# Power_Supplies.net
KiCad netlist of a schematic drawn in Altium Designer
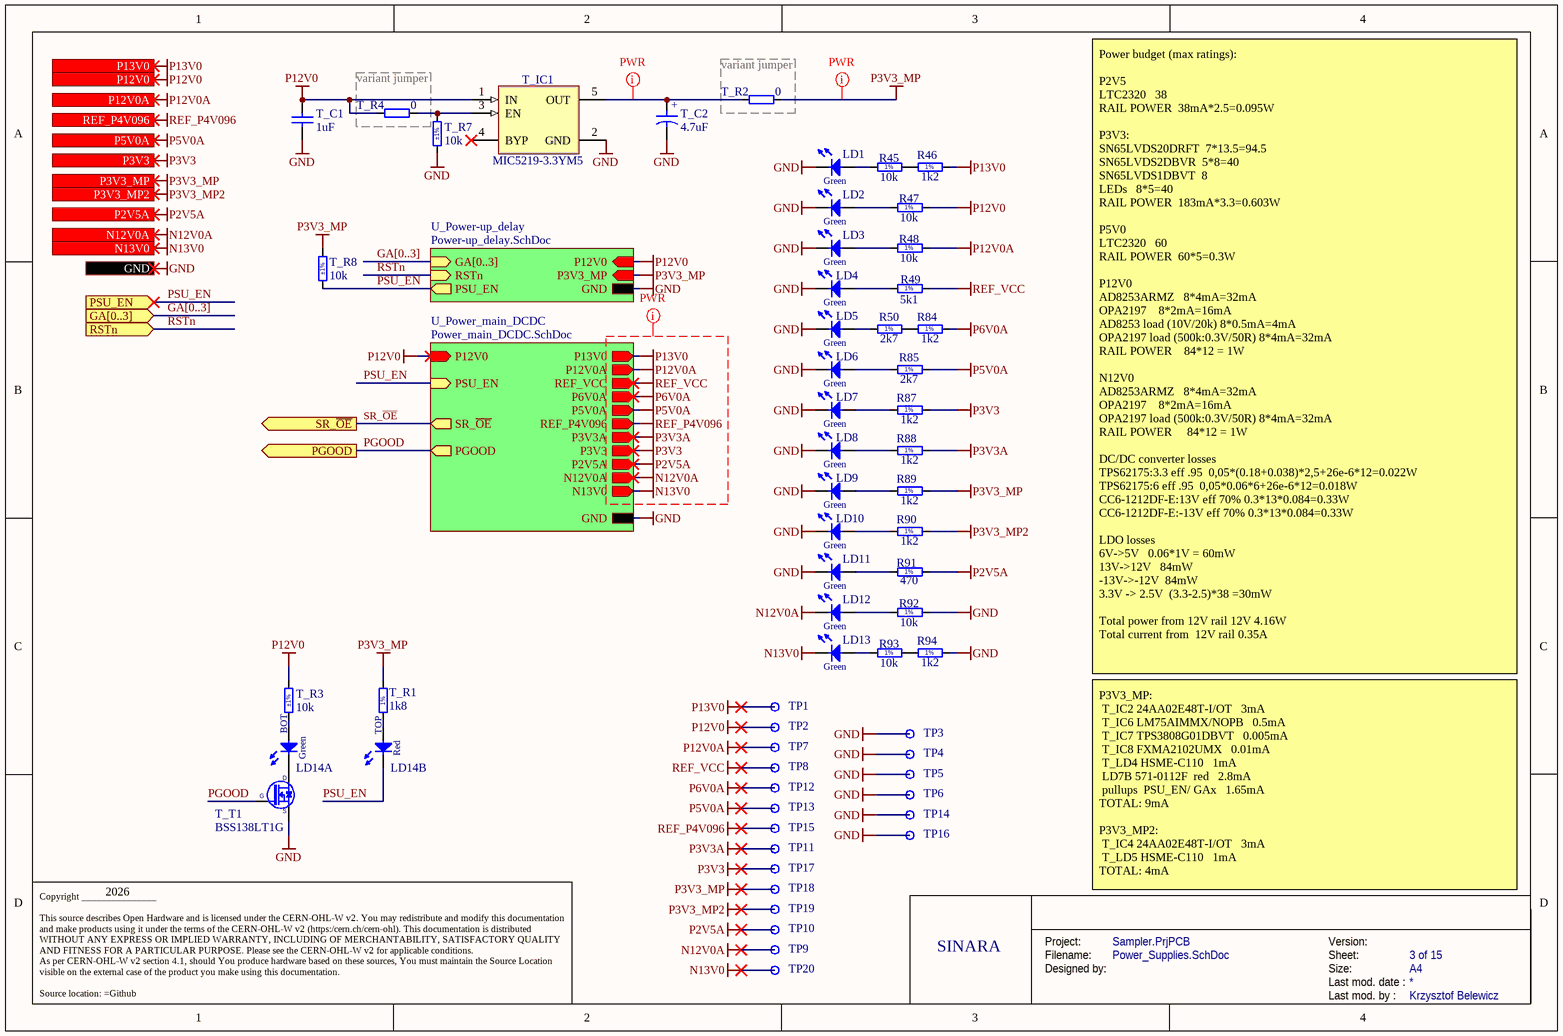
[diagram p0: Power_Supplies.SchDoc]

(export (version "E")
  (design (tool "Eeschema 10.0.6"))
  (components
    (comp (ref "LD1")
      (value "Green")
      (footprint "LED_KINGBRIGHT_KPH-1608CGCK")
      (description "LED Green 1C 2A")
      (fields
        (field (name "PART NUMBER") "LED_KINGBRIGHT_KPH-1608CGCK")
        (field (name "MANUFACTURER") "KINGBRIGHT")
        (field (name "AUTHOR") "CERN DEM JLC")
      )
      (libsource (lib "ICs And Semiconductors") (part "LED Green 1C 2A"))
    )
    (comp (ref "LD2")
      (value "Green")
      (footprint "LED_KINGBRIGHT_KPH-1608CGCK")
      (description "LED Green 1C 2A")
      (fields
        (field (name "PART NUMBER") "LED_KINGBRIGHT_KPH-1608CGCK")
        (field (name "MANUFACTURER") "KINGBRIGHT")
        (field (name "AUTHOR") "CERN DEM JLC")
      )
      (libsource (lib "ICs And Semiconductors") (part "LED Green 1C 2A"))
    )
    (comp (ref "LD3")
      (value "Green")
      (footprint "LED_KINGBRIGHT_KPH-1608CGCK")
      (description "LED Green 1C 2A")
      (fields
        (field (name "PART NUMBER") "LED_KINGBRIGHT_KPH-1608CGCK")
        (field (name "MANUFACTURER") "KINGBRIGHT")
        (field (name "AUTHOR") "CERN DEM JLC")
      )
      (libsource (lib "ICs And Semiconductors") (part "LED Green 1C 2A"))
    )
    (comp (ref "LD4")
      (value "Green")
      (footprint "LED_KINGBRIGHT_KPH-1608CGCK")
      (description "LED Green 1C 2A")
      (fields
        (field (name "PART NUMBER") "LED_KINGBRIGHT_KPH-1608CGCK")
        (field (name "MANUFACTURER") "KINGBRIGHT")
        (field (name "AUTHOR") "CERN DEM JLC")
      )
      (libsource (lib "ICs And Semiconductors") (part "LED Green 1C 2A"))
    )
    (comp (ref "LD5")
      (value "Green")
      (footprint "LED_KINGBRIGHT_KPH-1608CGCK")
      (description "LED Green 1C 2A")
      (fields
        (field (name "PART NUMBER") "LED_KINGBRIGHT_KPH-1608CGCK")
        (field (name "MANUFACTURER") "KINGBRIGHT")
        (field (name "AUTHOR") "CERN DEM JLC")
      )
      (libsource (lib "ICs And Semiconductors") (part "LED Green 1C 2A"))
    )
    (comp (ref "LD6")
      (value "Green")
      (footprint "LED_KINGBRIGHT_KPH-1608CGCK")
      (description "LED Green 1C 2A")
      (fields
        (field (name "PART NUMBER") "LED_KINGBRIGHT_KPH-1608CGCK")
        (field (name "MANUFACTURER") "KINGBRIGHT")
        (field (name "AUTHOR") "CERN DEM JLC")
      )
      (libsource (lib "ICs And Semiconductors") (part "LED Green 1C 2A"))
    )
    (comp (ref "LD7")
      (value "Green")
      (footprint "LED_KINGBRIGHT_KPH-1608CGCK")
      (description "LED Green 1C 2A")
      (fields
        (field (name "PART NUMBER") "LED_KINGBRIGHT_KPH-1608CGCK")
        (field (name "MANUFACTURER") "KINGBRIGHT")
        (field (name "AUTHOR") "CERN DEM JLC")
      )
      (libsource (lib "ICs And Semiconductors") (part "LED Green 1C 2A"))
    )
    (comp (ref "LD8")
      (value "Green")
      (footprint "LED_KINGBRIGHT_KPH-1608CGCK")
      (description "LED Green 1C 2A")
      (fields
        (field (name "PART NUMBER") "LED_KINGBRIGHT_KPH-1608CGCK")
        (field (name "MANUFACTURER") "KINGBRIGHT")
        (field (name "AUTHOR") "CERN DEM JLC")
      )
      (libsource (lib "ICs And Semiconductors") (part "LED Green 1C 2A"))
    )
    (comp (ref "LD9")
      (value "Green")
      (footprint "LED_KINGBRIGHT_KPH-1608CGCK")
      (description "LED Green 1C 2A")
      (fields
        (field (name "PART NUMBER") "LED_KINGBRIGHT_KPH-1608CGCK")
        (field (name "MANUFACTURER") "KINGBRIGHT")
        (field (name "AUTHOR") "CERN DEM JLC")
      )
      (libsource (lib "ICs And Semiconductors") (part "LED Green 1C 2A"))
    )
    (comp (ref "LD10")
      (value "Green")
      (footprint "LED_KINGBRIGHT_KPH-1608CGCK")
      (description "LED Green 1C 2A")
      (fields
        (field (name "PART NUMBER") "LED_KINGBRIGHT_KPH-1608CGCK")
        (field (name "MANUFACTURER") "KINGBRIGHT")
        (field (name "AUTHOR") "CERN DEM JLC")
      )
      (libsource (lib "ICs And Semiconductors") (part "LED Green 1C 2A"))
    )
    (comp (ref "LD11")
      (value "Green")
      (footprint "LED_KINGBRIGHT_KPH-1608CGCK")
      (description "LED Green 1C 2A")
      (fields
        (field (name "PART NUMBER") "LED_KINGBRIGHT_KPH-1608CGCK")
        (field (name "MANUFACTURER") "KINGBRIGHT")
        (field (name "AUTHOR") "CERN DEM JLC")
      )
      (libsource (lib "ICs And Semiconductors") (part "LED Green 1C 2A"))
    )
    (comp (ref "LD12")
      (value "Green")
      (footprint "LED_KINGBRIGHT_KPH-1608CGCK")
      (description "LED Green 1C 2A")
      (fields
        (field (name "PART NUMBER") "LED_KINGBRIGHT_KPH-1608CGCK")
        (field (name "MANUFACTURER") "KINGBRIGHT")
        (field (name "AUTHOR") "CERN DEM JLC")
      )
      (libsource (lib "ICs And Semiconductors") (part "LED Green 1C 2A"))
    )
    (comp (ref "LD13")
      (value "Green")
      (footprint "LED_KINGBRIGHT_KPH-1608CGCK")
      (description "LED Green 1C 2A")
      (fields
        (field (name "PART NUMBER") "LED_KINGBRIGHT_KPH-1608CGCK")
        (field (name "MANUFACTURER") "KINGBRIGHT")
        (field (name "AUTHOR") "CERN DEM JLC")
      )
      (libsource (lib "ICs And Semiconductors") (part "LED Green 1C 2A"))
    )
    (comp (ref "LD14")
      (value "Red/Green")
      (footprint "LED_DIALIGHT_571-0112F")
      (description "2x LED  Botom Green, Top Red")
      (fields
        (field (name "PART NUMBER") "LED_DIALIGHT_571-0112F")
        (field (name "MANUFACTURER") "DIALIGHT")
        (field (name "AUTHOR") "CERN DEM JLC")
      )
      (libsource (lib "ICs And Semiconductors") (part "LED x2 G-1C2A-BOT_R-3C4A-TOP"))
    )
    (comp (ref "R45")
      (value "10k")
      (footprint "RESC1005X40N")
      (description "Resistor - 1%")
      (fields
        (field (name "PART NUMBER") "R0402_10K_1%_0.0625W_100PPM")
        (field (name "POWER") "0.0625W")
        (field (name "AUTHOR") "CERN DEM JLC")
      )
      (libsource (lib "") (part "Resistor - 1%_1"))
    )
    (comp (ref "R46")
      (value "1k2")
      (footprint "RESC1608X55N")
      (description "Resistor - 1%")
      (fields
        (field (name "PART NUMBER") "R0603_1K2_1%_0.1W_100PPM")
        (field (name "POWER") "0.1W")
        (field (name "AUTHOR") "CERN DEM JLC")
      )
      (libsource (lib "Resistors") (part "Resistor - 1%"))
    )
    (comp (ref "R47")
      (value "10k")
      (footprint "RESC1005X40N")
      (description "Resistor - 1%")
      (fields
        (field (name "PART NUMBER") "R0402_10K_1%_0.0625W_100PPM")
        (field (name "POWER") "0.0625W")
        (field (name "AUTHOR") "CERN DEM JLC")
      )
      (libsource (lib "") (part "Resistor - 1%_1"))
    )
    (comp (ref "R48")
      (value "10k")
      (footprint "RESC1005X40N")
      (description "Resistor - 1%")
      (fields
        (field (name "PART NUMBER") "R0402_10K_1%_0.0625W_100PPM")
        (field (name "POWER") "0.0625W")
        (field (name "AUTHOR") "CERN DEM JLC")
      )
      (libsource (lib "") (part "Resistor - 1%_1"))
    )
    (comp (ref "R49")
      (value "5k1")
      (footprint "RESC1005X40N")
      (description "Resistor - 1%")
      (fields
        (field (name "PART NUMBER") "R0402_5K1_1%_0.0625W_100PPM")
        (field (name "POWER") "0.0625W")
        (field (name "AUTHOR") "CERN DEM JLC")
      )
      (libsource (lib "") (part "Resistor - 1%_1"))
    )
    (comp (ref "R50")
      (value "2k7")
      (footprint "RESC1608X55N")
      (description "Resistor - 1%")
      (fields
        (field (name "PART NUMBER") "R0603_2K7_1%_0.1W_100PPM")
        (field (name "POWER") "0.1W")
        (field (name "AUTHOR") "CERN DEM JLC")
      )
      (libsource (lib "Resistors") (part "Resistor - 1%"))
    )
    (comp (ref "R84")
      (value "1k2")
      (footprint "RESC1608X55N")
      (description "Resistor - 1%")
      (fields
        (field (name "PART NUMBER") "R0603_1K2_1%_0.1W_100PPM")
        (field (name "POWER") "0.1W")
        (field (name "AUTHOR") "CERN DEM JLC")
      )
      (libsource (lib "Resistors") (part "Resistor - 1%"))
    )
    (comp (ref "R85")
      (value "2k7")
      (footprint "RESC1608X55N")
      (description "Resistor - 1%")
      (fields
        (field (name "PART NUMBER") "R0603_2K7_1%_0.1W_100PPM")
        (field (name "POWER") "0.1W")
        (field (name "AUTHOR") "CERN DEM JLC")
      )
      (libsource (lib "Resistors") (part "Resistor - 1%"))
    )
    (comp (ref "R87")
      (value "1k2")
      (footprint "RESC1608X55N")
      (description "Resistor - 1%")
      (fields
        (field (name "PART NUMBER") "R0603_1K2_1%_0.1W_100PPM")
        (field (name "POWER") "0.1W")
        (field (name "AUTHOR") "CERN DEM JLC")
      )
      (libsource (lib "Resistors") (part "Resistor - 1%"))
    )
    (comp (ref "R88")
      (value "1k2")
      (footprint "RESC1608X55N")
      (description "Resistor - 1%")
      (fields
        (field (name "PART NUMBER") "R0603_1K2_1%_0.1W_100PPM")
        (field (name "POWER") "0.1W")
        (field (name "AUTHOR") "CERN DEM JLC")
      )
      (libsource (lib "Resistors") (part "Resistor - 1%"))
    )
    (comp (ref "R89")
      (value "1k2")
      (footprint "RESC1608X55N")
      (description "Resistor - 1%")
      (fields
        (field (name "PART NUMBER") "R0603_1K2_1%_0.1W_100PPM")
        (field (name "POWER") "0.1W")
        (field (name "AUTHOR") "CERN DEM JLC")
      )
      (libsource (lib "Resistors") (part "Resistor - 1%"))
    )
    (comp (ref "R90")
      (value "1k2")
      (footprint "RESC1608X55N")
      (description "Resistor - 1%")
      (fields
        (field (name "PART NUMBER") "R0603_1K2_1%_0.1W_100PPM")
        (field (name "POWER") "0.1W")
        (field (name "AUTHOR") "CERN DEM JLC")
      )
      (libsource (lib "Resistors") (part "Resistor - 1%"))
    )
    (comp (ref "R91")
      (value "470")
      (footprint "RESC1005X40N")
      (description "Resistor - 1%")
      (fields
        (field (name "PART NUMBER") "R0402_470R_1%_0.0625W_100PPM")
        (field (name "POWER") "0.0625W")
        (field (name "AUTHOR") "CERN DEM JLC")
      )
      (libsource (lib "") (part "Resistor - 1%_1"))
    )
    (comp (ref "R92")
      (value "10k")
      (footprint "RESC1005X40N")
      (description "Resistor - 1%")
      (fields
        (field (name "PART NUMBER") "R0402_10K_1%_0.0625W_100PPM")
        (field (name "POWER") "0.0625W")
        (field (name "AUTHOR") "CERN DEM JLC")
      )
      (libsource (lib "") (part "Resistor - 1%_1"))
    )
    (comp (ref "R93")
      (value "10k")
      (footprint "RESC1005X40N")
      (description "Resistor - 1%")
      (fields
        (field (name "PART NUMBER") "R0402_10K_1%_0.0625W_100PPM")
        (field (name "POWER") "0.0625W")
        (field (name "AUTHOR") "CERN DEM JLC")
      )
      (libsource (lib "") (part "Resistor - 1%_1"))
    )
    (comp (ref "R94")
      (value "1k2")
      (footprint "RESC1608X55N")
      (description "Resistor - 1%")
      (fields
        (field (name "PART NUMBER") "R0603_1K2_1%_0.1W_100PPM")
        (field (name "POWER") "0.1W")
        (field (name "AUTHOR") "CERN DEM JLC")
      )
      (libsource (lib "Resistors") (part "Resistor - 1%"))
    )
    (comp (ref "TP1")
      (value "Test Point")
      (footprint "TPS127")
      (fields (field (name "PART NUMBER") "SMD_PAD_1.27X1.27MM") (field (name "AUTHOR") "CERN DEM JLC"))
      (libsource (lib "Eletro-mechanical") (part "Test Point"))
    )
    (comp (ref "TP2")
      (value "Test Point")
      (footprint "TPS127")
      (fields (field (name "PART NUMBER") "SMD_PAD_1.27X1.27MM") (field (name "AUTHOR") "CERN DEM JLC"))
      (libsource (lib "Eletro-mechanical") (part "Test Point"))
    )
    (comp (ref "TP3")
      (value "Test Point")
      (footprint "TPS127")
      (fields (field (name "PART NUMBER") "SMD_PAD_1.27X1.27MM") (field (name "AUTHOR") "CERN DEM JLC"))
      (libsource (lib "Eletro-mechanical") (part "Test Point"))
    )
    (comp (ref "TP4")
      (value "Test Point")
      (footprint "TPS127")
      (fields (field (name "PART NUMBER") "SMD_PAD_1.27X1.27MM") (field (name "AUTHOR") "CERN DEM JLC"))
      (libsource (lib "Eletro-mechanical") (part "Test Point"))
    )
    (comp (ref "TP5")
      (value "Test Point")
      (footprint "TPS127")
      (fields (field (name "PART NUMBER") "SMD_PAD_1.27X1.27MM") (field (name "AUTHOR") "CERN DEM JLC"))
      (libsource (lib "Eletro-mechanical") (part "Test Point"))
    )
    (comp (ref "TP6")
      (value "Test Point")
      (footprint "TPS127")
      (fields (field (name "PART NUMBER") "SMD_PAD_1.27X1.27MM") (field (name "AUTHOR") "CERN DEM JLC"))
      (libsource (lib "Eletro-mechanical") (part "Test Point"))
    )
    (comp (ref "TP7")
      (value "Test Point")
      (footprint "TPS127")
      (fields (field (name "PART NUMBER") "SMD_PAD_1.27X1.27MM") (field (name "AUTHOR") "CERN DEM JLC"))
      (libsource (lib "Eletro-mechanical") (part "Test Point"))
    )
    (comp (ref "TP8")
      (value "Test Point")
      (footprint "TPS127")
      (fields (field (name "PART NUMBER") "SMD_PAD_1.27X1.27MM") (field (name "AUTHOR") "CERN DEM JLC"))
      (libsource (lib "Eletro-mechanical") (part "Test Point"))
    )
    (comp (ref "TP9")
      (value "Test Point")
      (footprint "TPS127")
      (fields (field (name "PART NUMBER") "SMD_PAD_1.27X1.27MM") (field (name "AUTHOR") "CERN DEM JLC"))
      (libsource (lib "Eletro-mechanical") (part "Test Point"))
    )
    (comp (ref "TP10")
      (value "Test Point")
      (footprint "TPS127")
      (fields (field (name "PART NUMBER") "SMD_PAD_1.27X1.27MM") (field (name "AUTHOR") "CERN DEM JLC"))
      (libsource (lib "Eletro-mechanical") (part "Test Point"))
    )
    (comp (ref "TP11")
      (value "Test Point")
      (footprint "TPS127")
      (fields (field (name "PART NUMBER") "SMD_PAD_1.27X1.27MM") (field (name "AUTHOR") "CERN DEM JLC"))
      (libsource (lib "Eletro-mechanical") (part "Test Point"))
    )
    (comp (ref "TP12")
      (value "Test Point")
      (footprint "TPS127")
      (fields (field (name "PART NUMBER") "SMD_PAD_1.27X1.27MM") (field (name "AUTHOR") "CERN DEM JLC"))
      (libsource (lib "Eletro-mechanical") (part "Test Point"))
    )
    (comp (ref "TP13")
      (value "Test Point")
      (footprint "TPS127")
      (fields (field (name "PART NUMBER") "SMD_PAD_1.27X1.27MM") (field (name "AUTHOR") "CERN DEM JLC"))
      (libsource (lib "Eletro-mechanical") (part "Test Point"))
    )
    (comp (ref "TP14")
      (value "Test Point")
      (footprint "TPS127")
      (fields (field (name "PART NUMBER") "SMD_PAD_1.27X1.27MM") (field (name "AUTHOR") "CERN DEM JLC"))
      (libsource (lib "Eletro-mechanical") (part "Test Point"))
    )
    (comp (ref "TP15")
      (value "Test Point")
      (footprint "TPS127")
      (fields (field (name "PART NUMBER") "SMD_PAD_1.27X1.27MM") (field (name "AUTHOR") "CERN DEM JLC"))
      (libsource (lib "Eletro-mechanical") (part "Test Point"))
    )
    (comp (ref "TP16")
      (value "Test Point")
      (footprint "TPS127")
      (fields (field (name "PART NUMBER") "SMD_PAD_1.27X1.27MM") (field (name "AUTHOR") "CERN DEM JLC"))
      (libsource (lib "Eletro-mechanical") (part "Test Point"))
    )
    (comp (ref "TP17")
      (value "Test Point")
      (footprint "TPS127")
      (fields (field (name "PART NUMBER") "SMD_PAD_1.27X1.27MM") (field (name "AUTHOR") "CERN DEM JLC"))
      (libsource (lib "Eletro-mechanical") (part "Test Point"))
    )
    (comp (ref "TP18")
      (value "Test Point")
      (footprint "TPS127")
      (fields (field (name "PART NUMBER") "SMD_PAD_1.27X1.27MM") (field (name "AUTHOR") "CERN DEM JLC"))
      (libsource (lib "Eletro-mechanical") (part "Test Point"))
    )
    (comp (ref "TP19")
      (value "Test Point")
      (footprint "TPS127")
      (fields (field (name "PART NUMBER") "SMD_PAD_1.27X1.27MM") (field (name "AUTHOR") "CERN DEM JLC"))
      (libsource (lib "Eletro-mechanical") (part "Test Point"))
    )
    (comp (ref "TP20")
      (value "Test Point")
      (footprint "TPS127")
      (fields (field (name "PART NUMBER") "SMD_PAD_1.27X1.27MM") (field (name "AUTHOR") "CERN DEM JLC"))
      (libsource (lib "Eletro-mechanical") (part "Test Point"))
    )
    (comp (ref "T_C1")
      (value "1uF")
      (footprint "CAPC1608X87N")
      (description "Non-polarised capacitor")
      (fields
        (field (name "PART NUMBER") "CC0603_1UF_25V_10%_X7R")
        (field (name "VOLTAGE") "25V")
        (field (name "AUTHOR") "CERN DEM JLC")
      )
      (libsource (lib "Capacitors") (part "Capacitor - non polarized"))
    )
    (comp (ref "T_C2")
      (value "4.7uF")
      (footprint "CAPMP3216X180N")
      (description "Polarised capacitor")
      (fields
        (field (name "PART NUMBER") "CTE3216-18_4.7UF_10V_10%_AVX_TPSA475K010T1400")
        (field (name "VOLTAGE") "10V")
        (field (name "AUTHOR") "CERN DEM JLC")
      )
      (libsource (lib "Capacitors") (part "Capacitor - polarized"))
    )
    (comp (ref "T_IC1")
      (value "MIC5219-3.3YM5")
      (footprint "SOT95P280X145-5N")
      (description "500mA Peak Output LDO Regulator")
      (fields (field (name "MANUFACTURER") "MICROCHIP TECHNOLOGY") (field (name "AUTHOR") "CERN DEM WB"))
      (libsource (lib "ICs And Semiconductors") (part "MIC5219-X.XYM5"))
    )
    (comp (ref "T_R1")
      (value "1k8")
      (footprint "RESC1608X55N")
      (description "Resistor - 1%")
      (fields
        (field (name "PART NUMBER") "R0603_1K8_1%_0.1W_100PPM")
        (field (name "POWER") "0.1W")
        (field (name "AUTHOR") "CERN DEM JLC")
      )
      (libsource (lib "Resistors") (part "Resistor - 1%"))
    )
    (comp (ref "T_R2")
      (value "0")
      (footprint "RESC1005X40N")
      (description "Resistor")
      (fields
        (field (name "PART NUMBER") "R0402_0R_JUMPER")
        (field (name "MANUFACTURER") "GENERIC")
        (field (name "AUTHOR") "CERN DEM JLC")
      )
      (libsource (lib "Resistors") (part "Resistor"))
    )
    (comp (ref "T_R3")
      (value "10k")
      (footprint "RESC1005X40N")
      (description "Resistor - 1%")
      (fields
        (field (name "TOLERANCE") "±1%")
        (field (name "PART NUMBER") "R0402_10K_1%_0.0625W_100PPM")
        (field (name "POWER") "0.0625W")
        (field (name "AUTHOR") "CERN DEM JLC")
      )
      (libsource (lib "") (part "Resistor - 1%_1"))
    )
    (comp (ref "T_R4")
      (value "0")
      (footprint "RESC1005X40N")
      (description "Resistor")
      (fields
        (field (name "PART NUMBER") "R0402_0R_JUMPER")
        (field (name "MANUFACTURER") "GENERIC")
        (field (name "AUTHOR") "CERN DEM JLC")
      )
      (libsource (lib "Resistors") (part "Resistor"))
    )
    (comp (ref "T_R7")
      (value "10k")
      (footprint "RESC1005X40N")
      (description "Resistor - 1%")
      (fields
        (field (name "TOLERANCE") "±1%")
        (field (name "PART NUMBER") "R0402_10K_1%_0.0625W_100PPM")
        (field (name "POWER") "0.0625W")
        (field (name "AUTHOR") "CERN DEM JLC")
      )
      (libsource (lib "") (part "Resistor - 1%_1"))
    )
    (comp (ref "T_R8")
      (value "10k")
      (footprint "RESC1005X40N")
      (description "Resistor - 1%")
      (fields
        (field (name "TOLERANCE") "±1%")
        (field (name "PART NUMBER") "R0402_10K_1%_0.0625W_100PPM")
        (field (name "POWER") "0.0625W")
        (field (name "AUTHOR") "CERN DEM JLC")
      )
      (libsource (lib "") (part "Resistor - 1%_1"))
    )
    (comp (ref "T_T1")
      (value "BSS138LT1G")
      (footprint "SOT95P240X110-3N")
      (description "N-CHANNEL MOSFET WITH DIODE")
      (fields
        (field (name "MANUFACTURER") "ON SEMICONDUCTOR")
        (field (name "MANUFACTURER PART NUMBER") "BSS138L")
        (field (name "AUTHOR") "CERN DEM JLC")
      )
      (libsource (lib "ICs And Semiconductors") (part "N-MOSFET-D 1G 2S 3D"))
    )
  )
  (nets
    (net (code "6") (name "/PGOOD") (class "Default")
      (node (ref "T_T1") (pin "1") (pinfunction "G_1") (pintype "passive"))
    )
    (net (code "7") (name "/PSU_EN") (class "Default")
      (node (ref "LD14") (pin "3") (pinfunction "C_3") (pintype "passive"))
      (node (ref "T_R8") (pin "1") (pinfunction "1_1") (pintype "passive"))
    )
    (net (code "10") (name "GND") (class "Default")
      (node (ref "LD1") (pin "1") (pinfunction "C_1") (pintype "passive"))
      (node (ref "LD10") (pin "1") (pinfunction "C_1") (pintype "passive"))
      (node (ref "LD11") (pin "1") (pinfunction "C_1") (pintype "passive"))
      (node (ref "LD2") (pin "1") (pinfunction "C_1") (pintype "passive"))
      (node (ref "LD3") (pin "1") (pinfunction "C_1") (pintype "passive"))
      (node (ref "LD4") (pin "1") (pinfunction "C_1") (pintype "passive"))
      (node (ref "LD5") (pin "1") (pinfunction "C_1") (pintype "passive"))
      (node (ref "LD6") (pin "1") (pinfunction "C_1") (pintype "passive"))
      (node (ref "LD7") (pin "1") (pinfunction "C_1") (pintype "passive"))
      (node (ref "LD8") (pin "1") (pinfunction "C_1") (pintype "passive"))
      (node (ref "LD9") (pin "1") (pinfunction "C_1") (pintype "passive"))
      (node (ref "R92") (pin "2") (pinfunction "2_2") (pintype "passive"))
      (node (ref "R94") (pin "2") (pinfunction "2_2") (pintype "passive"))
      (node (ref "TP14") (pin "1") (pinfunction "1_1") (pintype "bidirectional"))
      (node (ref "TP16") (pin "1") (pinfunction "1_1") (pintype "bidirectional"))
      (node (ref "TP3") (pin "1") (pinfunction "1_1") (pintype "bidirectional"))
      (node (ref "TP4") (pin "1") (pinfunction "1_1") (pintype "bidirectional"))
      (node (ref "TP5") (pin "1") (pinfunction "1_1") (pintype "bidirectional"))
      (node (ref "TP6") (pin "1") (pinfunction "1_1") (pintype "bidirectional"))
      (node (ref "T_C1") (pin "1") (pinfunction "1_1") (pintype "passive"))
      (node (ref "T_C2") (pin "2") (pinfunction "2_2") (pintype "passive"))
      (node (ref "T_IC1") (pin "2") (pinfunction "GND_2") (pintype "power_in"))
      (node (ref "T_R7") (pin "1") (pinfunction "1_1") (pintype "passive"))
      (node (ref "T_T1") (pin "2") (pinfunction "S_2") (pintype "passive"))
    )
    (net (code "11") (name "N12V0A") (class "Default")
      (node (ref "LD12") (pin "1") (pinfunction "C_1") (pintype "passive"))
      (node (ref "TP9") (pin "1") (pinfunction "1_1") (pintype "bidirectional"))
    )
    (net (code "12") (name "N13V0") (class "Default")
      (node (ref "LD13") (pin "1") (pinfunction "C_1") (pintype "passive"))
      (node (ref "TP20") (pin "1") (pinfunction "1_1") (pintype "bidirectional"))
    )
    (net (code "13") (name "Net-(LD1-A)") (class "Default")
      (node (ref "LD1") (pin "2") (pinfunction "A_2") (pintype "passive"))
      (node (ref "R45") (pin "1") (pinfunction "1_1") (pintype "passive"))
    )
    (net (code "14") (name "Net-(LD2-A)") (class "Default")
      (node (ref "LD2") (pin "2") (pinfunction "A_2") (pintype "passive"))
      (node (ref "R47") (pin "1") (pinfunction "1_1") (pintype "passive"))
    )
    (net (code "15") (name "Net-(LD3-A)") (class "Default")
      (node (ref "LD3") (pin "2") (pinfunction "A_2") (pintype "passive"))
      (node (ref "R48") (pin "1") (pinfunction "1_1") (pintype "passive"))
    )
    (net (code "16") (name "Net-(LD4-A)") (class "Default")
      (node (ref "LD4") (pin "2") (pinfunction "A_2") (pintype "passive"))
      (node (ref "R49") (pin "1") (pinfunction "1_1") (pintype "passive"))
    )
    (net (code "17") (name "Net-(LD5-A)") (class "Default")
      (node (ref "LD5") (pin "2") (pinfunction "A_2") (pintype "passive"))
      (node (ref "R50") (pin "1") (pinfunction "1_1") (pintype "passive"))
    )
    (net (code "18") (name "Net-(LD6-A)") (class "Default")
      (node (ref "LD6") (pin "2") (pinfunction "A_2") (pintype "passive"))
      (node (ref "R85") (pin "1") (pinfunction "1_1") (pintype "passive"))
    )
    (net (code "19") (name "Net-(LD7-A)") (class "Default")
      (node (ref "LD7") (pin "2") (pinfunction "A_2") (pintype "passive"))
      (node (ref "R87") (pin "1") (pinfunction "1_1") (pintype "passive"))
    )
    (net (code "20") (name "Net-(LD8-A)") (class "Default")
      (node (ref "LD8") (pin "2") (pinfunction "A_2") (pintype "passive"))
      (node (ref "R88") (pin "1") (pinfunction "1_1") (pintype "passive"))
    )
    (net (code "21") (name "Net-(LD9-A)") (class "Default")
      (node (ref "LD9") (pin "2") (pinfunction "A_2") (pintype "passive"))
      (node (ref "R89") (pin "1") (pinfunction "1_1") (pintype "passive"))
    )
    (net (code "22") (name "Net-(LD10-A)") (class "Default")
      (node (ref "LD10") (pin "2") (pinfunction "A_2") (pintype "passive"))
      (node (ref "R90") (pin "1") (pinfunction "1_1") (pintype "passive"))
    )
    (net (code "23") (name "Net-(LD11-A)") (class "Default")
      (node (ref "LD11") (pin "2") (pinfunction "A_2") (pintype "passive"))
      (node (ref "R91") (pin "2") (pinfunction "2_2") (pintype "passive"))
    )
    (net (code "24") (name "Net-(LD12-A)") (class "Default")
      (node (ref "LD12") (pin "2") (pinfunction "A_2") (pintype "passive"))
      (node (ref "R92") (pin "1") (pinfunction "1_1") (pintype "passive"))
    )
    (net (code "25") (name "Net-(LD13-A)") (class "Default")
      (node (ref "LD13") (pin "2") (pinfunction "A_2") (pintype "passive"))
      (node (ref "R93") (pin "1") (pinfunction "1_1") (pintype "passive"))
    )
    (net (code "26") (name "Net-(LD14A-A)") (class "Default")
      (node (ref "LD14") (pin "2") (pinfunction "A_2") (pintype "passive"))
      (node (ref "T_R3") (pin "1") (pinfunction "1_1") (pintype "passive"))
    )
    (net (code "27") (name "Net-(LD14A-C)") (class "Default")
      (node (ref "LD14") (pin "1") (pinfunction "C_1") (pintype "passive"))
      (node (ref "T_T1") (pin "3") (pinfunction "D_3") (pintype "passive"))
    )
    (net (code "28") (name "Net-(LD14B-A)") (class "Default")
      (node (ref "LD14") (pin "4") (pinfunction "A_4") (pintype "passive"))
      (node (ref "T_R1") (pin "1") (pinfunction "1_1") (pintype "passive"))
    )
    (net (code "29") (name "Net-(R45-Pad2)") (class "Default")
      (node (ref "R45") (pin "2") (pinfunction "2_2") (pintype "passive"))
      (node (ref "R46") (pin "1") (pinfunction "1_1") (pintype "passive"))
    )
    (net (code "30") (name "Net-(R50-Pad2)") (class "Default")
      (node (ref "R50") (pin "2") (pinfunction "2_2") (pintype "passive"))
      (node (ref "R84") (pin "1") (pinfunction "1_1") (pintype "passive"))
    )
    (net (code "31") (name "Net-(R93-Pad2)") (class "Default")
      (node (ref "R93") (pin "2") (pinfunction "2_2") (pintype "passive"))
      (node (ref "R94") (pin "1") (pinfunction "1_1") (pintype "passive"))
    )
    (net (code "32") (name "Net-(T_IC1-EN)") (class "Default")
      (node (ref "T_IC1") (pin "3") (pinfunction "EN_3") (pintype "input"))
      (node (ref "T_R4") (pin "2") (pinfunction "2_2") (pintype "passive"))
      (node (ref "T_R7") (pin "2") (pinfunction "2_2") (pintype "passive"))
    )
    (net (code "33") (name "Net-(T_IC1-OUT)") (class "Default")
      (node (ref "T_C2") (pin "1") (pinfunction "1_1") (pintype "passive"))
      (node (ref "T_IC1") (pin "5") (pinfunction "OUT_5") (pintype "power_in"))
      (node (ref "T_R2") (pin "1") (pinfunction "1_1") (pintype "passive"))
    )
    (net (code "34") (name "P2V5A") (class "Default")
      (node (ref "R91") (pin "1") (pinfunction "1_1") (pintype "passive"))
      (node (ref "TP10") (pin "1") (pinfunction "1_1") (pintype "bidirectional"))
    )
    (net (code "35") (name "P3V3") (class "Default")
      (node (ref "R87") (pin "2") (pinfunction "2_2") (pintype "passive"))
      (node (ref "TP17") (pin "1") (pinfunction "1_1") (pintype "bidirectional"))
    )
    (net (code "36") (name "P3V3A") (class "Default")
      (node (ref "R88") (pin "2") (pinfunction "2_2") (pintype "passive"))
      (node (ref "TP11") (pin "1") (pinfunction "1_1") (pintype "bidirectional"))
    )
    (net (code "37") (name "P3V3_MP") (class "Default")
      (node (ref "R89") (pin "2") (pinfunction "2_2") (pintype "passive"))
      (node (ref "TP18") (pin "1") (pinfunction "1_1") (pintype "bidirectional"))
      (node (ref "T_R1") (pin "2") (pinfunction "2_2") (pintype "passive"))
      (node (ref "T_R2") (pin "2") (pinfunction "2_2") (pintype "passive"))
      (node (ref "T_R8") (pin "2") (pinfunction "2_2") (pintype "passive"))
    )
    (net (code "38") (name "P3V3_MP2") (class "Default")
      (node (ref "R90") (pin "2") (pinfunction "2_2") (pintype "passive"))
      (node (ref "TP19") (pin "1") (pinfunction "1_1") (pintype "bidirectional"))
    )
    (net (code "39") (name "P5V0A") (class "Default")
      (node (ref "R85") (pin "2") (pinfunction "2_2") (pintype "passive"))
      (node (ref "TP13") (pin "1") (pinfunction "1_1") (pintype "bidirectional"))
    )
    (net (code "40") (name "P6V0A") (class "Default")
      (node (ref "R84") (pin "2") (pinfunction "2_2") (pintype "passive"))
      (node (ref "TP12") (pin "1") (pinfunction "1_1") (pintype "bidirectional"))
    )
    (net (code "41") (name "P12V0") (class "Default")
      (node (ref "R47") (pin "2") (pinfunction "2_2") (pintype "passive"))
      (node (ref "TP2") (pin "1") (pinfunction "1_1") (pintype "bidirectional"))
      (node (ref "T_C1") (pin "2") (pinfunction "2_2") (pintype "passive"))
      (node (ref "T_IC1") (pin "1") (pinfunction "IN_1") (pintype "input"))
      (node (ref "T_R3") (pin "2") (pinfunction "2_2") (pintype "passive"))
      (node (ref "T_R4") (pin "1") (pinfunction "1_1") (pintype "passive"))
    )
    (net (code "42") (name "P12V0A") (class "Default")
      (node (ref "R48") (pin "2") (pinfunction "2_2") (pintype "passive"))
      (node (ref "TP7") (pin "1") (pinfunction "1_1") (pintype "bidirectional"))
    )
    (net (code "43") (name "P13V0") (class "Default")
      (node (ref "R46") (pin "2") (pinfunction "2_2") (pintype "passive"))
      (node (ref "TP1") (pin "1") (pinfunction "1_1") (pintype "bidirectional"))
    )
    (net (code "44") (name "REF_P4V096") (class "Default")
      (node (ref "TP15") (pin "1") (pinfunction "1_1") (pintype "bidirectional"))
    )
    (net (code "45") (name "REF_VCC") (class "Default")
      (node (ref "R49") (pin "2") (pinfunction "2_2") (pintype "passive"))
      (node (ref "TP8") (pin "1") (pinfunction "1_1") (pintype "bidirectional"))
    )
    (net (code "46") (name "unconnected-(T_IC1-BYP-Pad4)") (class "Default")
      (node (ref "T_IC1") (pin "4") (pinfunction "BYP_4") (pintype "passive+no_connect"))
    )
  )
)
